# Vumetro-v1.net
KiCad netlist of a schematic drawn in EAGLE
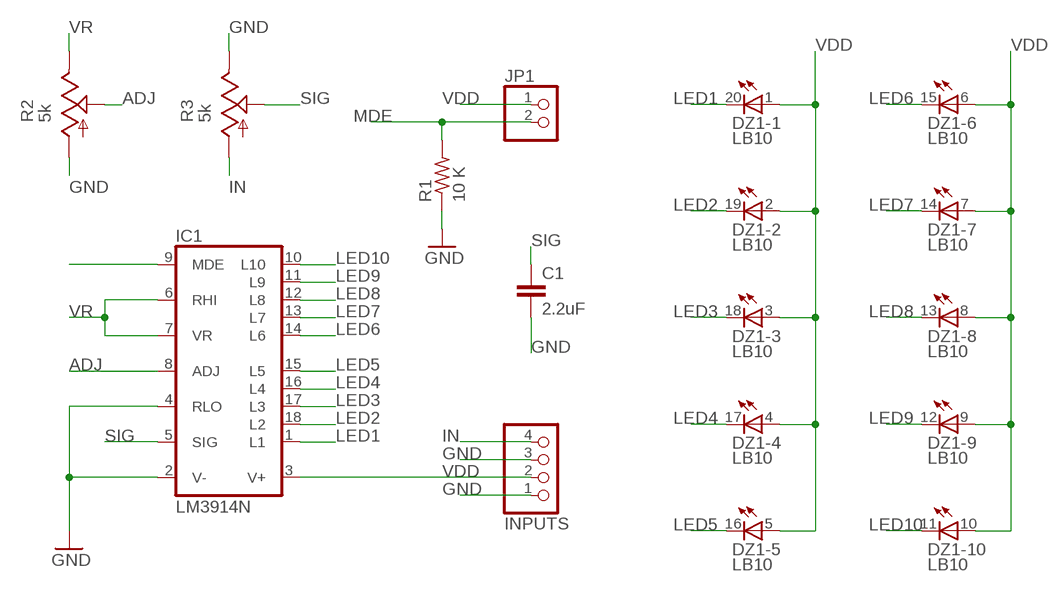
[diagram p0: schematic, sheet 1]

(export (version "E")
  (design (tool "Eeschema 10.0.6"))
  (components
    (comp (ref "C1")
      (value "2.2uF")
      (footprint "eagle-import:C2.5-6")
      (libsource (lib "eagle-import") (part "C2.5/6"))
    )
    (comp (ref "DZ1")
      (value "LB10")
      (footprint "eagle-import:LB10")
      (libsource (lib "eagle-import") (part "LB10"))
    )
    (comp (ref "IC1")
      (value "LM3914N")
      (footprint "eagle-import:DIL18")
      (libsource (lib "eagle-import") (part "LM3914N"))
    )
    (comp (ref "INPUTS")
      (value "PINHD-1X4")
      (footprint "eagle-import:1X04")
      (libsource (lib "eagle-import") (part "PINHD-1X4"))
    )
    (comp (ref "JP1")
      (value "PINHD-1X2")
      (footprint "eagle-import:1X02")
      (libsource (lib "eagle-import") (part "PINHD-1X2"))
    )
    (comp (ref "R1")
      (value "10 K")
      (footprint "eagle-import:0204_5")
      (libsource (lib "eagle-import") (part "R-US_0204/5"))
    )
    (comp (ref "R2")
      (value "5k")
      (footprint "eagle-import:PT-10")
      (libsource (lib "eagle-import") (part "TRIM_US-PT10"))
    )
    (comp (ref "R3")
      (value "5k")
      (footprint "eagle-import:PT-10")
      (libsource (lib "eagle-import") (part "TRIM_US-PT10"))
    )
  )
  (nets
    (net (code "1") (name "/ADJ") (class "Default")
      (node (ref "IC1") (pin "8") (pinfunction "ADJ_8") (pintype "input"))
      (node (ref "R2") (pin "S") (pinfunction "S_S") (pintype "passive"))
    )
    (net (code "2") (name "/IN") (class "Default")
      (node (ref "INPUTS") (pin "4") (pinfunction "4_4") (pintype "passive"))
      (node (ref "R3") (pin "A") (pinfunction "A_A") (pintype "passive"))
    )
    (net (code "3") (name "/LED1") (class "Default")
      (node (ref "DZ1") (pin "20") (pinfunction "C_20") (pintype "passive"))
      (node (ref "IC1") (pin "1") (pinfunction "L1_1") (pintype "output"))
    )
    (net (code "4") (name "/LED2") (class "Default")
      (node (ref "DZ1") (pin "19") (pinfunction "C_19") (pintype "passive"))
      (node (ref "IC1") (pin "18") (pinfunction "L2_18") (pintype "output"))
    )
    (net (code "5") (name "/LED3") (class "Default")
      (node (ref "DZ1") (pin "18") (pinfunction "C_18") (pintype "passive"))
      (node (ref "IC1") (pin "17") (pinfunction "L3_17") (pintype "output"))
    )
    (net (code "6") (name "/LED4") (class "Default")
      (node (ref "DZ1") (pin "17") (pinfunction "C_17") (pintype "passive"))
      (node (ref "IC1") (pin "16") (pinfunction "L4_16") (pintype "output"))
    )
    (net (code "7") (name "/LED5") (class "Default")
      (node (ref "DZ1") (pin "16") (pinfunction "C_16") (pintype "passive"))
      (node (ref "IC1") (pin "15") (pinfunction "L5_15") (pintype "output"))
    )
    (net (code "8") (name "/LED6") (class "Default")
      (node (ref "DZ1") (pin "15") (pinfunction "C_15") (pintype "passive"))
      (node (ref "IC1") (pin "14") (pinfunction "L6_14") (pintype "output"))
    )
    (net (code "9") (name "/LED7") (class "Default")
      (node (ref "DZ1") (pin "14") (pinfunction "C_14") (pintype "passive"))
      (node (ref "IC1") (pin "13") (pinfunction "L7_13") (pintype "output"))
    )
    (net (code "10") (name "/LED8") (class "Default")
      (node (ref "DZ1") (pin "13") (pinfunction "C_13") (pintype "passive"))
      (node (ref "IC1") (pin "12") (pinfunction "L8_12") (pintype "output"))
    )
    (net (code "11") (name "/LED9") (class "Default")
      (node (ref "DZ1") (pin "12") (pinfunction "C_12") (pintype "passive"))
      (node (ref "IC1") (pin "11") (pinfunction "L9_11") (pintype "output"))
    )
    (net (code "12") (name "/LED10") (class "Default")
      (node (ref "DZ1") (pin "11") (pinfunction "C_11") (pintype "passive"))
      (node (ref "IC1") (pin "10") (pinfunction "L10_10") (pintype "output"))
    )
    (net (code "13") (name "/MDE") (class "Default")
      (node (ref "IC1") (pin "9") (pinfunction "MDE_9") (pintype "input"))
      (node (ref "JP1") (pin "2") (pinfunction "2_2") (pintype "passive"))
      (node (ref "R1") (pin "2") (pinfunction "2_2") (pintype "passive"))
    )
    (net (code "14") (name "/SIG") (class "Default")
      (node (ref "C1") (pin "1") (pinfunction "1_1") (pintype "passive"))
      (node (ref "IC1") (pin "5") (pinfunction "SIG_5") (pintype "input"))
      (node (ref "R3") (pin "S") (pinfunction "S_S") (pintype "passive"))
    )
    (net (code "15") (name "/VDD") (class "Default")
      (node (ref "DZ1") (pin "1") (pinfunction "A_1") (pintype "passive"))
      (node (ref "DZ1") (pin "10") (pinfunction "A_10") (pintype "passive"))
      (node (ref "DZ1") (pin "2") (pinfunction "A_2") (pintype "passive"))
      (node (ref "DZ1") (pin "3") (pinfunction "A_3") (pintype "passive"))
      (node (ref "DZ1") (pin "4") (pinfunction "A_4") (pintype "passive"))
      (node (ref "DZ1") (pin "5") (pinfunction "A_5") (pintype "passive"))
      (node (ref "DZ1") (pin "6") (pinfunction "A_6") (pintype "passive"))
      (node (ref "DZ1") (pin "7") (pinfunction "A_7") (pintype "passive"))
      (node (ref "DZ1") (pin "8") (pinfunction "A_8") (pintype "passive"))
      (node (ref "DZ1") (pin "9") (pinfunction "A_9") (pintype "passive"))
      (node (ref "IC1") (pin "3") (pinfunction "V+_3") (pintype "power_in"))
      (node (ref "INPUTS") (pin "2") (pinfunction "2_2") (pintype "passive"))
      (node (ref "JP1") (pin "1") (pinfunction "1_1") (pintype "passive"))
    )
    (net (code "16") (name "/VR") (class "Default")
      (node (ref "IC1") (pin "6") (pinfunction "RHI_6") (pintype "input"))
      (node (ref "IC1") (pin "7") (pinfunction "VR_7") (pintype "output"))
      (node (ref "R2") (pin "E") (pinfunction "E_E") (pintype "passive"))
    )
    (net (code "17") (name "GND") (class "Default")
      (node (ref "C1") (pin "2") (pinfunction "2_2") (pintype "passive"))
      (node (ref "IC1") (pin "2") (pinfunction "V-_2") (pintype "power_in"))
      (node (ref "IC1") (pin "4") (pinfunction "RLO_4") (pintype "input"))
      (node (ref "INPUTS") (pin "1") (pinfunction "1_1") (pintype "passive"))
      (node (ref "INPUTS") (pin "3") (pinfunction "3_3") (pintype "passive"))
      (node (ref "R1") (pin "1") (pinfunction "1_1") (pintype "passive"))
      (node (ref "R2") (pin "A") (pinfunction "A_A") (pintype "passive"))
      (node (ref "R3") (pin "E") (pinfunction "E_E") (pintype "passive"))
    )
  )
)
